# TinyS3Controller.net
KiCad netlist of a schematic drawn in EAGLE
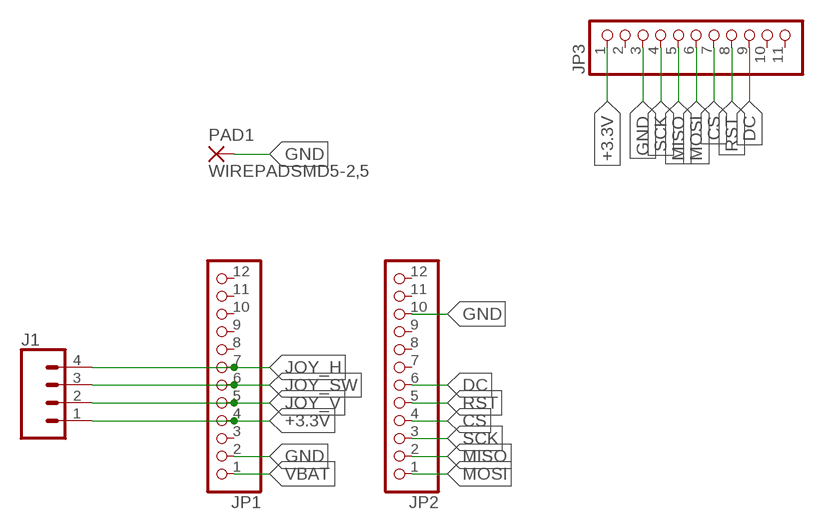
[diagram p0: schematic, sheet 1]

(export (version "E")
  (design (tool "Eeschema 10.0.6"))
  (components
    (comp (ref "J1")
      (value "CONN_04PTH")
      (footprint "eagle-import:1X04")
      (libsource (lib "eagle-import") (part "CONN_04PTH"))
    )
    (comp (ref "JP1")
      (value "PINHD-1X12-CB")
      (footprint "eagle-import:1X12-CB")
      (libsource (lib "eagle-import") (part "PINHD-1X12-CB"))
    )
    (comp (ref "JP2")
      (value "PINHD-1X12-CB")
      (footprint "eagle-import:1X12-CB")
      (libsource (lib "eagle-import") (part "PINHD-1X12-CB"))
    )
    (comp (ref "JP3")
      (value "PINHD-1X11")
      (footprint "eagle-import:1X11")
      (libsource (lib "eagle-import") (part "PINHD-1X11"))
    )
    (comp (ref "PAD1")
      (value "WIREPADSMD5-2,5")
      (footprint "eagle-import:5-2,5")
      (libsource (lib "eagle-import") (part "WIREPADSMD5-2,5"))
    )
  )
  (nets
    (net (code "1") (name "+3.3V") (class "Default")
      (node (ref "J1") (pin "1") (pinfunction "1_1") (pintype "passive"))
      (node (ref "JP1") (pin "4") (pinfunction "4_4") (pintype "passive"))
      (node (ref "JP3") (pin "1") (pinfunction "1_1") (pintype "passive"))
    )
    (net (code "2") (name "CS") (class "Default")
      (node (ref "JP2") (pin "4") (pinfunction "4_4") (pintype "passive"))
      (node (ref "JP3") (pin "7") (pinfunction "7_7") (pintype "passive"))
    )
    (net (code "3") (name "DC") (class "Default")
      (node (ref "JP2") (pin "6") (pinfunction "6_6") (pintype "passive"))
      (node (ref "JP3") (pin "9") (pinfunction "9_9") (pintype "passive"))
    )
    (net (code "4") (name "GND") (class "Default")
      (node (ref "JP1") (pin "2") (pinfunction "2_2") (pintype "passive"))
      (node (ref "JP2") (pin "10") (pinfunction "10_10") (pintype "passive"))
      (node (ref "JP3") (pin "3") (pinfunction "3_3") (pintype "passive"))
      (node (ref "PAD1") (pin "1") (pinfunction "P_1") (pintype "passive"))
    )
    (net (code "5") (name "JOY_H") (class "Default")
      (node (ref "J1") (pin "4") (pinfunction "4_4") (pintype "passive"))
      (node (ref "JP1") (pin "7") (pinfunction "7_7") (pintype "passive"))
    )
    (net (code "6") (name "JOY_SW") (class "Default")
      (node (ref "J1") (pin "3") (pinfunction "3_3") (pintype "passive"))
      (node (ref "JP1") (pin "6") (pinfunction "6_6") (pintype "passive"))
    )
    (net (code "7") (name "JOY_V") (class "Default")
      (node (ref "J1") (pin "2") (pinfunction "2_2") (pintype "passive"))
      (node (ref "JP1") (pin "5") (pinfunction "5_5") (pintype "passive"))
    )
    (net (code "8") (name "MISO") (class "Default")
      (node (ref "JP2") (pin "2") (pinfunction "2_2") (pintype "passive"))
      (node (ref "JP3") (pin "5") (pinfunction "5_5") (pintype "passive"))
    )
    (net (code "9") (name "MOSI") (class "Default")
      (node (ref "JP2") (pin "1") (pinfunction "1_1") (pintype "passive"))
      (node (ref "JP3") (pin "6") (pinfunction "6_6") (pintype "passive"))
    )
    (net (code "10") (name "RST") (class "Default")
      (node (ref "JP2") (pin "5") (pinfunction "5_5") (pintype "passive"))
      (node (ref "JP3") (pin "8") (pinfunction "8_8") (pintype "passive"))
    )
    (net (code "11") (name "SCK") (class "Default")
      (node (ref "JP2") (pin "3") (pinfunction "3_3") (pintype "passive"))
      (node (ref "JP3") (pin "4") (pinfunction "4_4") (pintype "passive"))
    )
    (net (code "12") (name "VBAT") (class "Default")
      (node (ref "JP1") (pin "1") (pinfunction "1_1") (pintype "passive"))
    )
    (net (code "13") (name "unconnected-(JP1-Pad3)") (class "Default")
      (node (ref "JP1") (pin "3") (pinfunction "3_3") (pintype "passive"))
    )
    (net (code "14") (name "unconnected-(JP1-Pad8)") (class "Default")
      (node (ref "JP1") (pin "8") (pinfunction "8_8") (pintype "passive"))
    )
    (net (code "15") (name "unconnected-(JP1-Pad9)") (class "Default")
      (node (ref "JP1") (pin "9") (pinfunction "9_9") (pintype "passive"))
    )
    (net (code "16") (name "unconnected-(JP1-Pad10)") (class "Default")
      (node (ref "JP1") (pin "10") (pinfunction "10_10") (pintype "passive"))
    )
    (net (code "17") (name "unconnected-(JP1-Pad11)") (class "Default")
      (node (ref "JP1") (pin "11") (pinfunction "11_11") (pintype "passive"))
    )
    (net (code "18") (name "unconnected-(JP1-Pad12)") (class "Default")
      (node (ref "JP1") (pin "12") (pinfunction "12_12") (pintype "passive"))
    )
    (net (code "19") (name "unconnected-(JP2-Pad7)") (class "Default")
      (node (ref "JP2") (pin "7") (pinfunction "7_7") (pintype "passive"))
    )
    (net (code "20") (name "unconnected-(JP2-Pad8)") (class "Default")
      (node (ref "JP2") (pin "8") (pinfunction "8_8") (pintype "passive"))
    )
    (net (code "21") (name "unconnected-(JP2-Pad9)") (class "Default")
      (node (ref "JP2") (pin "9") (pinfunction "9_9") (pintype "passive"))
    )
    (net (code "22") (name "unconnected-(JP2-Pad11)") (class "Default")
      (node (ref "JP2") (pin "11") (pinfunction "11_11") (pintype "passive"))
    )
    (net (code "23") (name "unconnected-(JP2-Pad12)") (class "Default")
      (node (ref "JP2") (pin "12") (pinfunction "12_12") (pintype "passive"))
    )
    (net (code "24") (name "unconnected-(JP3-Pad2)") (class "Default")
      (node (ref "JP3") (pin "2") (pinfunction "2_2") (pintype "passive"))
    )
    (net (code "25") (name "unconnected-(JP3-Pad10)") (class "Default")
      (node (ref "JP3") (pin "10") (pinfunction "10_10") (pintype "passive"))
    )
    (net (code "26") (name "unconnected-(JP3-Pad11)") (class "Default")
      (node (ref "JP3") (pin "11") (pinfunction "11_11") (pintype "passive"))
    )
  )
)
